# twilight-esp.net
KiCad netlist of a schematic drawn in EAGLE
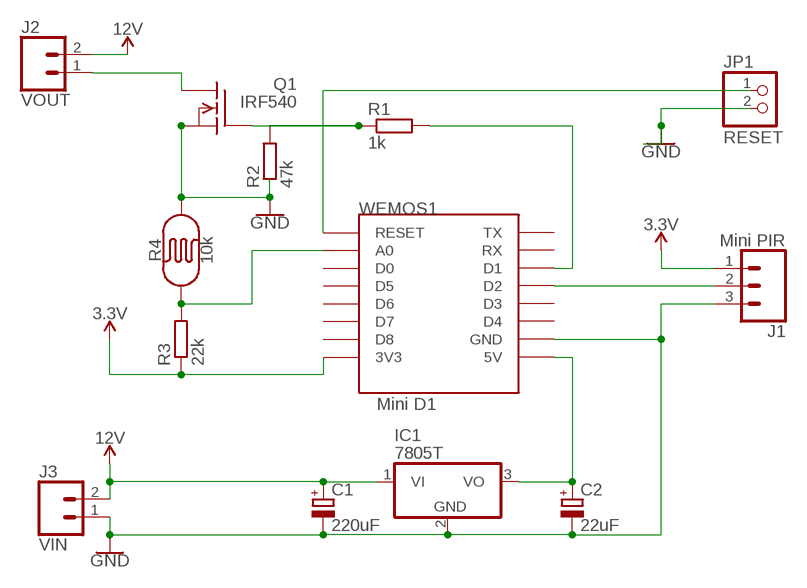
[diagram p0: schematic, sheet 1]

(export (version "E")
  (design (tool "Eeschema 10.0.6"))
  (components
    (comp (ref "C1")
      (value "220uF")
      (footprint "eagle-import:E2-5")
      (libsource (lib "eagle-import") (part "CPOL-EUE2-5"))
    )
    (comp (ref "C2")
      (value "22uF")
      (footprint "eagle-import:E2-4")
      (libsource (lib "eagle-import") (part "CPOL-EUE2-4"))
    )
    (comp (ref "IC1")
      (value "7805T")
      (footprint "eagle-import:TO220H")
      (libsource (lib "eagle-import") (part "78T05"))
    )
    (comp (ref "J1")
      (value "Mini PIR")
      (footprint "eagle-import:1X03")
      (libsource (lib "eagle-import") (part "CONN_03"))
    )
    (comp (ref "J2")
      (value "VOUT")
      (footprint "eagle-import:SCREWTERMINAL-5MM-2")
      (libsource (lib "eagle-import") (part "CONN_025MM"))
    )
    (comp (ref "J3")
      (value "VIN")
      (footprint "eagle-import:SCREWTERMINAL-5MM-2")
      (libsource (lib "eagle-import") (part "CONN_025MM"))
    )
    (comp (ref "JP1")
      (value "RESET")
      (footprint "eagle-import:1X02")
      (libsource (lib "eagle-import") (part "PINHD-1X2"))
    )
    (comp (ref "Q1")
      (value "IRF540")
      (footprint "eagle-import:TO220")
      (libsource (lib "eagle-import") (part "IRF540"))
    )
    (comp (ref "R1")
      (value "1k")
      (footprint "eagle-import:0207_7")
      (libsource (lib "eagle-import") (part "R-EU_0207/7"))
    )
    (comp (ref "R2")
      (value "47k")
      (footprint "eagle-import:0207_7")
      (libsource (lib "eagle-import") (part "R-EU_0207/7"))
    )
    (comp (ref "R3")
      (value "22k")
      (footprint "eagle-import:0207_7")
      (libsource (lib "eagle-import") (part "R-EU_0207/7"))
    )
    (comp (ref "R4")
      (value "10k")
      (footprint "eagle-import:PHOTOCELL")
      (libsource (lib "eagle-import") (part "PHOTOCELLPTH"))
    )
    (comp (ref "WEMOS1")
      (value "Mini D1")
      (footprint "eagle-import:WEMOS-D1-MINI")
      (libsource (lib "eagle-import") (part "WEMOS-D1-MINI"))
    )
  )
  (nets
    (net (code "1") (name "3.3V") (class "Default")
      (node (ref "J1") (pin "1") (pinfunction "1_1") (pintype "passive"))
      (node (ref "R3") (pin "1") (pinfunction "1_1") (pintype "passive"))
      (node (ref "WEMOS1") (pin "3V3") (pinfunction "3V3_3V3") (pintype "bidirectional"))
    )
    (net (code "2") (name "12V") (class "Default")
      (node (ref "C1") (pin "+") (pinfunction "+_+") (pintype "passive"))
      (node (ref "IC1") (pin "1") (pinfunction "VI_1") (pintype "input"))
      (node (ref "J2") (pin "2") (pinfunction "2_2") (pintype "passive"))
      (node (ref "J3") (pin "2") (pinfunction "2_2") (pintype "passive"))
    )
    (net (code "3") (name "GND") (class "Default")
      (node (ref "C1") (pin "-") (pinfunction "-_-") (pintype "passive"))
      (node (ref "C2") (pin "-") (pinfunction "-_-") (pintype "passive"))
      (node (ref "IC1") (pin "2") (pinfunction "GND_2") (pintype "passive"))
      (node (ref "J1") (pin "3") (pinfunction "3_3") (pintype "passive"))
      (node (ref "J3") (pin "1") (pinfunction "1_1") (pintype "passive"))
      (node (ref "JP1") (pin "2") (pinfunction "2_2") (pintype "passive"))
      (node (ref "Q1") (pin "3") (pinfunction "S_3") (pintype "passive"))
      (node (ref "R2") (pin "1") (pinfunction "1_1") (pintype "passive"))
      (node (ref "R4") (pin "2") (pinfunction "P$2_2") (pintype "bidirectional"))
      (node (ref "WEMOS1") (pin "GND") (pinfunction "GND_GND") (pintype "bidirectional"))
    )
    (net (code "4") (name "Net-(IC1-VO)") (class "Default")
      (node (ref "C2") (pin "+") (pinfunction "+_+") (pintype "passive"))
      (node (ref "IC1") (pin "3") (pinfunction "VO_3") (pintype "passive"))
      (node (ref "WEMOS1") (pin "5V") (pinfunction "5V_5V") (pintype "bidirectional"))
    )
    (net (code "5") (name "Net-(J1-Pad2)") (class "Default")
      (node (ref "J1") (pin "2") (pinfunction "2_2") (pintype "passive"))
      (node (ref "WEMOS1") (pin "D2") (pinfunction "D2_D2") (pintype "bidirectional"))
    )
    (net (code "6") (name "Net-(JP1-Pad1)") (class "Default")
      (node (ref "JP1") (pin "1") (pinfunction "1_1") (pintype "passive"))
      (node (ref "WEMOS1") (pin "RESET") (pinfunction "RESET_RESET") (pintype "bidirectional"))
    )
    (net (code "7") (name "Net-(Q1-D)") (class "Default")
      (node (ref "J2") (pin "1") (pinfunction "1_1") (pintype "passive"))
      (node (ref "Q1") (pin "2") (pinfunction "D_2") (pintype "passive"))
    )
    (net (code "8") (name "Net-(Q1-G)") (class "Default")
      (node (ref "Q1") (pin "1") (pinfunction "G_1") (pintype "passive"))
      (node (ref "R1") (pin "1") (pinfunction "1_1") (pintype "passive"))
      (node (ref "R2") (pin "2") (pinfunction "2_2") (pintype "passive"))
    )
    (net (code "9") (name "Net-(R1-Pad2)") (class "Default")
      (node (ref "R1") (pin "2") (pinfunction "2_2") (pintype "passive"))
      (node (ref "WEMOS1") (pin "D1") (pinfunction "D1_D1") (pintype "bidirectional"))
    )
    (net (code "10") (name "Net-(R4-P$1)") (class "Default")
      (node (ref "R3") (pin "2") (pinfunction "2_2") (pintype "passive"))
      (node (ref "R4") (pin "1") (pinfunction "P$1_1") (pintype "bidirectional"))
      (node (ref "WEMOS1") (pin "A0") (pinfunction "A0_A0") (pintype "bidirectional"))
    )
    (net (code "11") (name "unconnected-(WEMOS1-PadD0)") (class "Default")
      (node (ref "WEMOS1") (pin "D0") (pinfunction "D0_D0") (pintype "bidirectional"))
    )
    (net (code "12") (name "unconnected-(WEMOS1-PadD3)") (class "Default")
      (node (ref "WEMOS1") (pin "D3") (pinfunction "D3_D3") (pintype "bidirectional"))
    )
    (net (code "13") (name "unconnected-(WEMOS1-PadD4)") (class "Default")
      (node (ref "WEMOS1") (pin "D4") (pinfunction "D4_D4") (pintype "bidirectional"))
    )
    (net (code "14") (name "unconnected-(WEMOS1-PadD5)") (class "Default")
      (node (ref "WEMOS1") (pin "D5") (pinfunction "D5_D5") (pintype "bidirectional"))
    )
    (net (code "15") (name "unconnected-(WEMOS1-PadD6)") (class "Default")
      (node (ref "WEMOS1") (pin "D6") (pinfunction "D6_D6") (pintype "bidirectional"))
    )
    (net (code "16") (name "unconnected-(WEMOS1-PadD7)") (class "Default")
      (node (ref "WEMOS1") (pin "D7") (pinfunction "D7_D7") (pintype "bidirectional"))
    )
    (net (code "17") (name "unconnected-(WEMOS1-PadD8)") (class "Default")
      (node (ref "WEMOS1") (pin "D8") (pinfunction "D8_D8") (pintype "bidirectional"))
    )
    (net (code "18") (name "unconnected-(WEMOS1-PadRX)") (class "Default")
      (node (ref "WEMOS1") (pin "RX") (pinfunction "RX_RX") (pintype "bidirectional"))
    )
    (net (code "19") (name "unconnected-(WEMOS1-PadTX)") (class "Default")
      (node (ref "WEMOS1") (pin "TX") (pinfunction "TX_TX") (pintype "bidirectional"))
    )
  )
)
